# Clock2.net
KiCad netlist of a schematic drawn in EasyEDA Pro
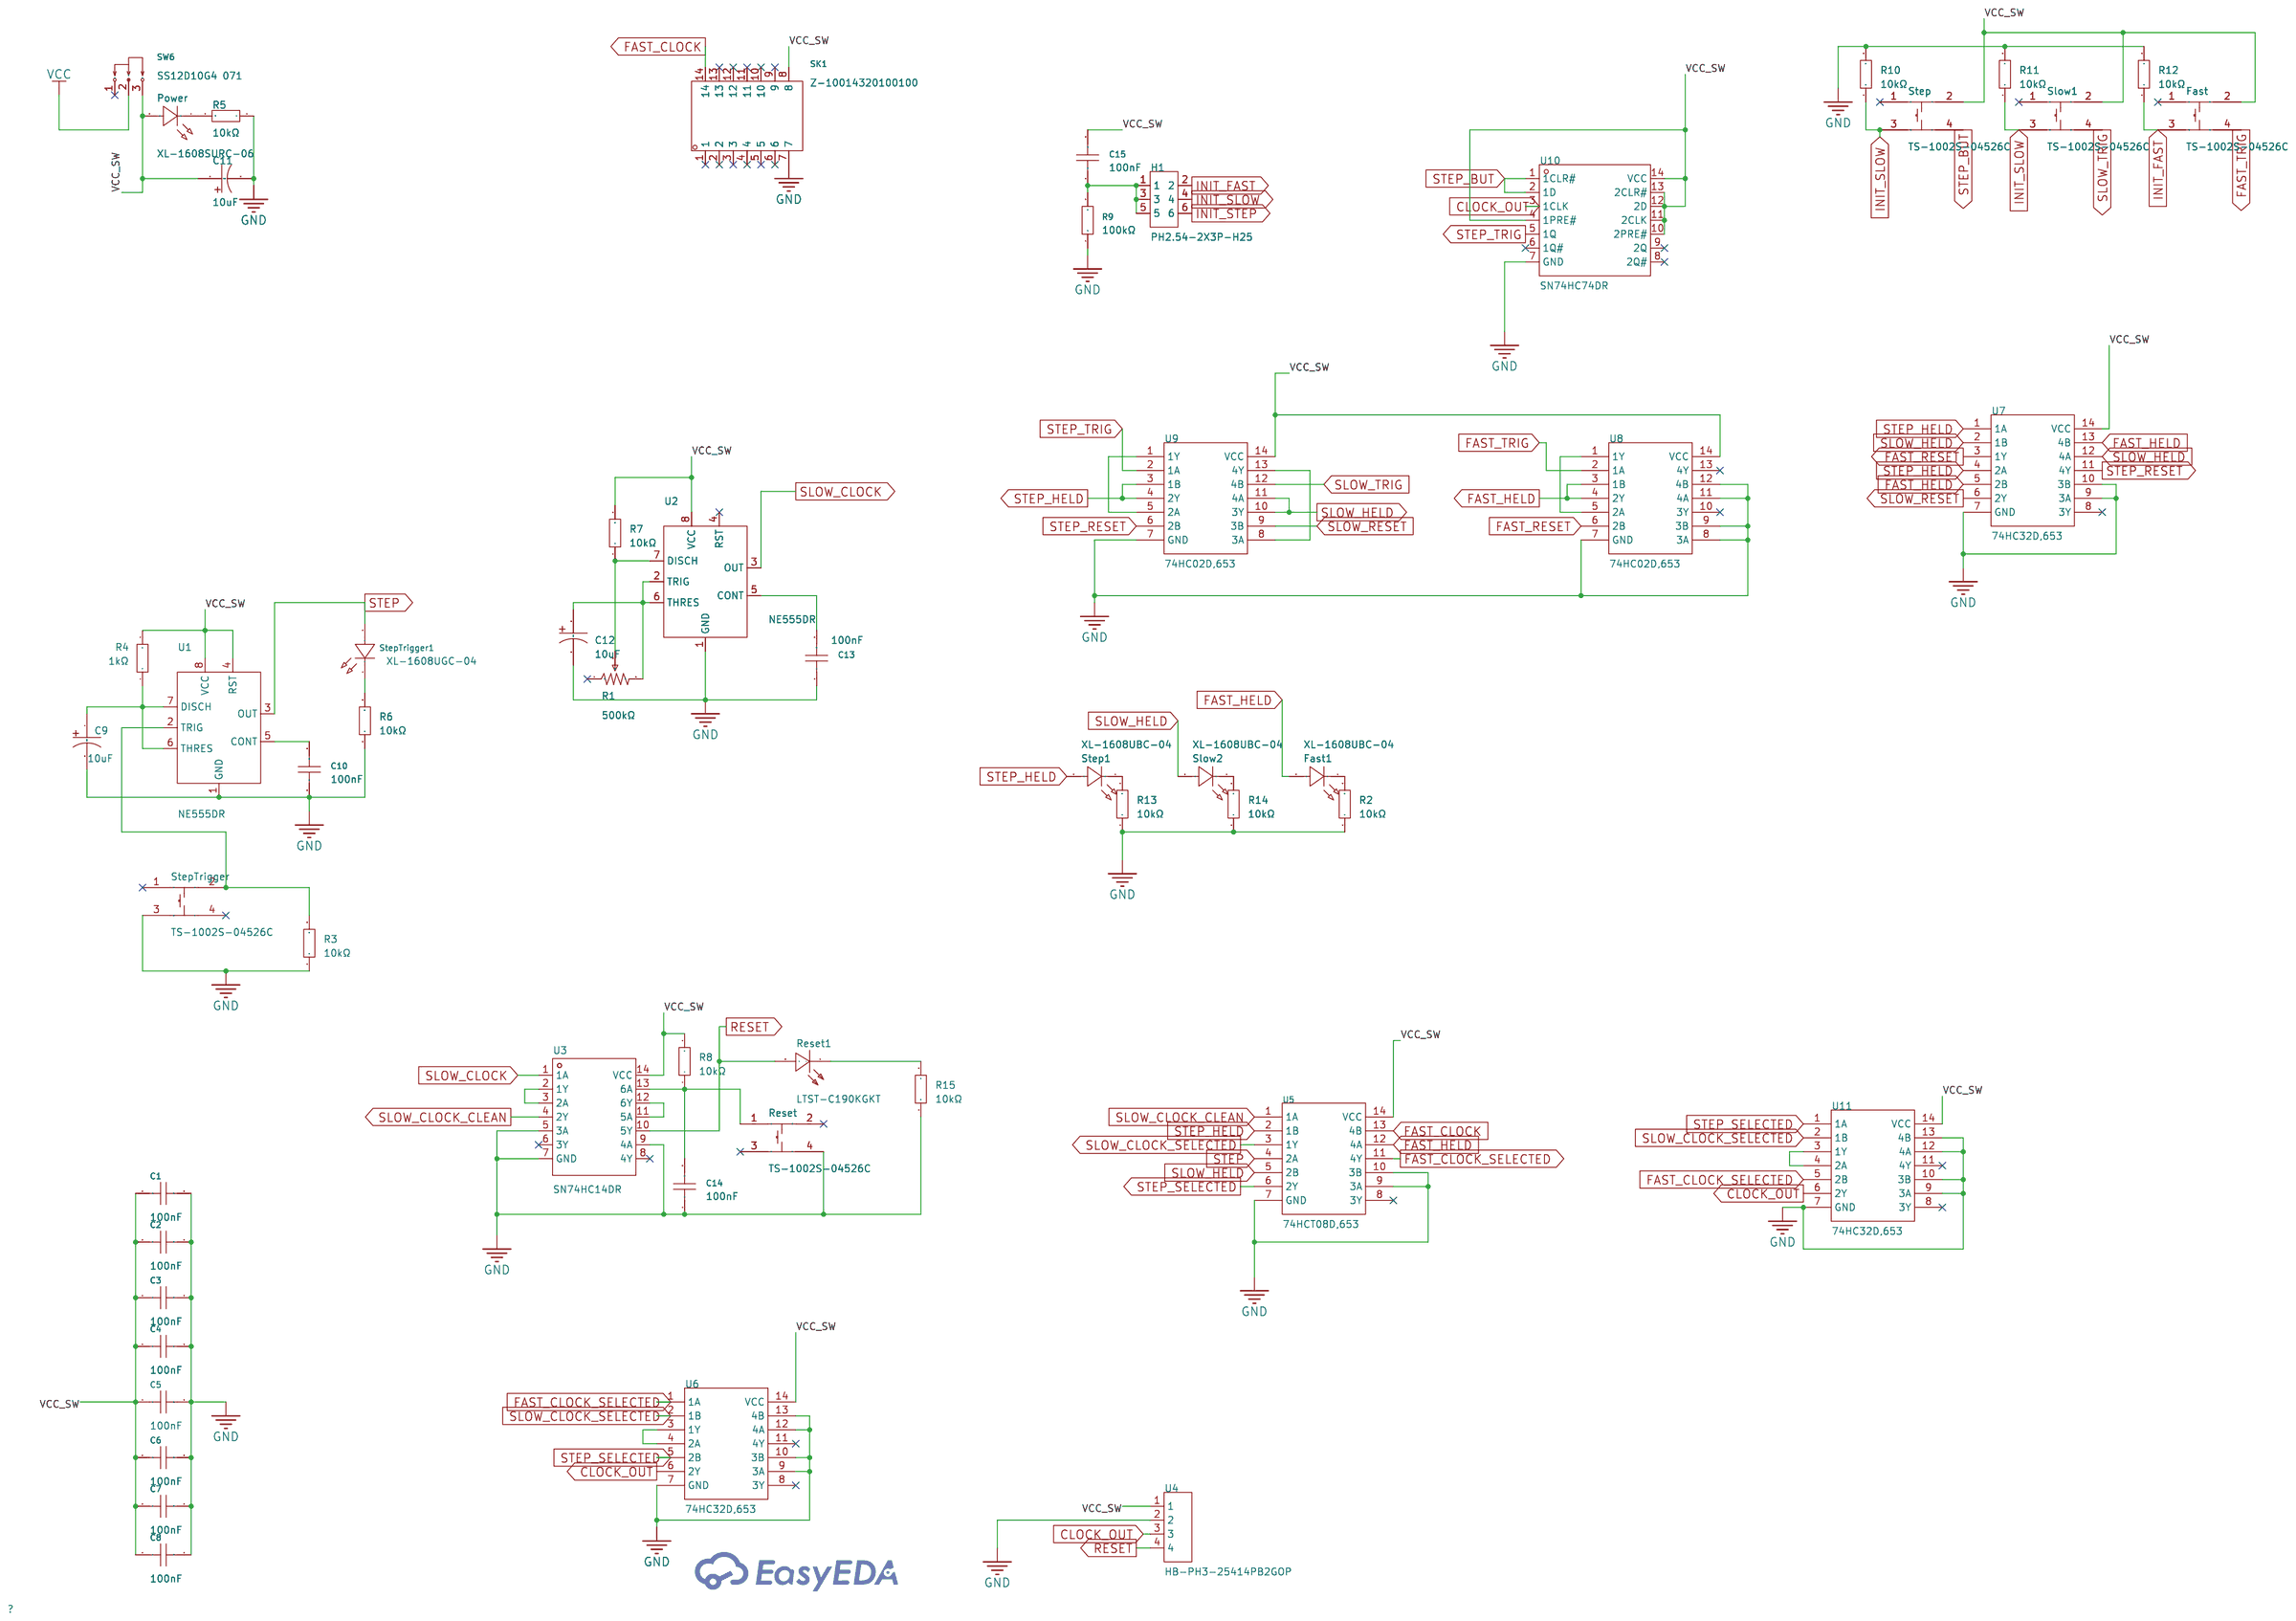
[diagram p0: schematic sheet]

(export (version "E")
  (design (tool "Eeschema 10.0.6"))
  (components
    (comp (ref "C1")
      (value "100nF")
      (footprint "easyedapro:C0603")
      (description "Capacitance:100nF Tolerance:±10% Tolerance:±10% Voltage Rating:50V Temperature Coefficient:X7R")
      (fields
        (field (name "Manufacturer Part") "CL10B104KB8NNNC")
        (field (name "Manufacturer") "SAMSUNG(三星)")
      )
      (libsource (lib "easyedapro") (part "CL10B104KB8NNNC"))
    )
    (comp (ref "C2")
      (value "100nF")
      (footprint "easyedapro:C0603")
      (description "Capacitance:100nF Tolerance:±10% Tolerance:±10% Voltage Rating:50V Temperature Coefficient:X7R")
      (fields
        (field (name "Manufacturer Part") "CL10B104KB8NNNC")
        (field (name "Manufacturer") "SAMSUNG(三星)")
      )
      (libsource (lib "easyedapro") (part "CL10B104KB8NNNC"))
    )
    (comp (ref "C3")
      (value "100nF")
      (footprint "easyedapro:C0603")
      (description "Capacitance:100nF Tolerance:±10% Tolerance:±10% Voltage Rating:50V Temperature Coefficient:X7R")
      (fields
        (field (name "Manufacturer Part") "CL10B104KB8NNNC")
        (field (name "Manufacturer") "SAMSUNG(三星)")
      )
      (libsource (lib "easyedapro") (part "CL10B104KB8NNNC"))
    )
    (comp (ref "C4")
      (value "100nF")
      (footprint "easyedapro:C0603")
      (description "Capacitance:100nF Tolerance:±10% Tolerance:±10% Voltage Rating:50V Temperature Coefficient:X7R")
      (fields
        (field (name "Manufacturer Part") "CL10B104KB8NNNC")
        (field (name "Manufacturer") "SAMSUNG(三星)")
      )
      (libsource (lib "easyedapro") (part "CL10B104KB8NNNC"))
    )
    (comp (ref "C5")
      (value "100nF")
      (footprint "easyedapro:C0603")
      (description "Capacitance:100nF Tolerance:±10% Tolerance:±10% Voltage Rating:50V Temperature Coefficient:X7R")
      (fields
        (field (name "Manufacturer Part") "CL10B104KB8NNNC")
        (field (name "Manufacturer") "SAMSUNG(三星)")
      )
      (libsource (lib "easyedapro") (part "CL10B104KB8NNNC"))
    )
    (comp (ref "C6")
      (value "100nF")
      (footprint "easyedapro:C0603")
      (description "Capacitance:100nF Tolerance:±10% Tolerance:±10% Voltage Rating:50V Temperature Coefficient:X7R")
      (fields
        (field (name "Manufacturer Part") "CL10B104KB8NNNC")
        (field (name "Manufacturer") "SAMSUNG(三星)")
      )
      (libsource (lib "easyedapro") (part "CL10B104KB8NNNC"))
    )
    (comp (ref "C7")
      (value "100nF")
      (footprint "easyedapro:C0603")
      (description "Capacitance:100nF Tolerance:±10% Tolerance:±10% Voltage Rating:50V Temperature Coefficient:X7R")
      (fields
        (field (name "Manufacturer Part") "CL10B104KB8NNNC")
        (field (name "Manufacturer") "SAMSUNG(三星)")
      )
      (libsource (lib "easyedapro") (part "CL10B104KB8NNNC"))
    )
    (comp (ref "C8")
      (value "100nF")
      (footprint "easyedapro:C0603")
      (description "Capacitance:100nF Tolerance:±10% Tolerance:±10% Voltage Rating:50V Temperature Coefficient:X7R")
      (fields
        (field (name "Manufacturer Part") "CL10B104KB8NNNC")
        (field (name "Manufacturer") "SAMSUNG(三星)")
      )
      (libsource (lib "easyedapro") (part "CL10B104KB8NNNC"))
    )
    (comp (ref "C9")
      (value "10uF")
      (footprint "easyedapro:CAP-TH_BD4.0-P1.50-D0.8-FD")
      (fields
        (field (name "Manufacturer Part") "KS1C100MB070A00CV0")
        (field (name "Manufacturer") "HUAWEI(华威集团)")
      )
      (libsource (lib "easyedapro") (part "KS1C100MB070A00CV0"))
    )
    (comp (ref "C10")
      (value "100nF")
      (footprint "easyedapro:C0603")
      (description "Capacitance:100nF Tolerance:±10% Tolerance:±10% Voltage Rating:50V Temperature Coefficient:X7R")
      (fields
        (field (name "Manufacturer Part") "CL10B104KB8NNNC")
        (field (name "Manufacturer") "SAMSUNG(三星)")
      )
      (libsource (lib "easyedapro") (part "CL10B104KB8NNNC"))
    )
    (comp (ref "C11")
      (value "10uF")
      (footprint "easyedapro:CAP-TH_BD4.0-P1.50-D0.8-FD")
      (fields
        (field (name "Manufacturer Part") "KS1C100MB070A00CV0")
        (field (name "Manufacturer") "HUAWEI(华威集团)")
      )
      (libsource (lib "easyedapro") (part "KS1C100MB070A00CV0"))
    )
    (comp (ref "C12")
      (value "10uF")
      (footprint "easyedapro:CAP-TH_BD4.0-P1.50-D0.8-FD")
      (fields
        (field (name "Manufacturer Part") "KS1C100MB070A00CV0")
        (field (name "Manufacturer") "HUAWEI(华威集团)")
      )
      (libsource (lib "easyedapro") (part "KS1C100MB070A00CV0"))
    )
    (comp (ref "C13")
      (value "100nF")
      (footprint "easyedapro:C0603")
      (description "Capacitance:100nF Tolerance:±10% Tolerance:±10% Voltage Rating:50V Temperature Coefficient:X7R")
      (fields
        (field (name "Manufacturer Part") "CL10B104KB8NNNC")
        (field (name "Manufacturer") "SAMSUNG(三星)")
      )
      (libsource (lib "easyedapro") (part "CL10B104KB8NNNC"))
    )
    (comp (ref "C14")
      (value "100nF")
      (footprint "easyedapro:C0603")
      (description "Capacitance:100nF Tolerance:±10% Tolerance:±10% Voltage Rating:50V Temperature Coefficient:X7R")
      (fields
        (field (name "Manufacturer Part") "CL10B104KB8NNNC")
        (field (name "Manufacturer") "SAMSUNG(三星)")
      )
      (libsource (lib "easyedapro") (part "CL10B104KB8NNNC"))
    )
    (comp (ref "C15")
      (value "100nF")
      (footprint "easyedapro:C0603")
      (description "Capacitance:100nF Tolerance:±10% Tolerance:±10% Voltage Rating:50V Temperature Coefficient:X7R")
      (fields
        (field (name "Manufacturer Part") "CL10B104KB8NNNC")
        (field (name "Manufacturer") "SAMSUNG(三星)")
      )
      (libsource (lib "easyedapro") (part "CL10B104KB8NNNC"))
    )
    (comp (ref "Fast")
      (value "TS-1002S-04526C")
      (footprint "easyedapro:SW-SMD_4P-L6.0-W6.0-P4.50-LS9.0-2")
      (fields (field (name "Manufacturer") "XUNPU(讯普)"))
      (libsource (lib "easyedapro") (part "TS-1002S-04526C"))
    )
    (comp (ref "Fast1")
      (value "XL-1608UBC-04")
      (footprint "easyedapro:LED0603-RD_BLUE")
      (fields (field (name "Manufacturer") "XINGLIGHT(成兴光)"))
      (libsource (lib "easyedapro") (part "XL-1608UBC-04"))
    )
    (comp (ref "H1")
      (value "PH2.54-2X3P-H25")
      (footprint "easyedapro:HDR-TH_6P-P2.54-V-M-R2-C3-S2.54-1")
      (fields (field (name "Manufacturer") "JXTCONN(聚兴泰)"))
      (libsource (lib "easyedapro") (part "PH2.54-2X3P-H25"))
    )
    (comp (ref "Power")
      (value "XL-1608SURC-06")
      (footprint "easyedapro:LED0603-RD_RED")
      (fields (field (name "Manufacturer") "XINGLIGHT(成兴光)"))
      (libsource (lib "easyedapro") (part "XL-1608SURC-06"))
    )
    (comp (ref "R1")
      (value "500kΩ")
      (footprint "easyedapro:RES-ADJ-TH_3P-L9.5-W9.5-P2.54-BL_3386P-EY5-504LF")
      (description "Resistance:500kΩ Voltage Rating:- Power(Watts):500mW Number of Turns:-")
      (fields (field (name "Manufacturer Part") "3386P-EY5-504LF") (field (name "Manufacturer") "BOURNS"))
      (libsource (lib "easyedapro") (part "3386P-EY5-504LF"))
    )
    (comp (ref "R2")
      (value "10kΩ")
      (footprint "easyedapro:R0603")
      (fields (field (name "Manufacturer Part") "RC0603FR-0710KL") (field (name "Manufacturer") "YAGEO(国巨)"))
      (libsource (lib "easyedapro") (part "RC0603FR-0710KL"))
    )
    (comp (ref "R3")
      (value "10kΩ")
      (footprint "easyedapro:R0603")
      (fields (field (name "Manufacturer Part") "RC0603FR-0710KL") (field (name "Manufacturer") "YAGEO(国巨)"))
      (libsource (lib "easyedapro") (part "RC0603FR-0710KL"))
    )
    (comp (ref "R4")
      (value "1kΩ")
      (footprint "easyedapro:R0603")
      (fields (field (name "Manufacturer Part") "RC0603FR-071KL") (field (name "Manufacturer") "YAGEO(国巨)"))
      (libsource (lib "easyedapro") (part "RC0603FR-071KL"))
    )
    (comp (ref "R5")
      (value "10kΩ")
      (footprint "easyedapro:R0603")
      (fields (field (name "Manufacturer Part") "RC0603FR-0710KL") (field (name "Manufacturer") "YAGEO(国巨)"))
      (libsource (lib "easyedapro") (part "RC0603FR-0710KL"))
    )
    (comp (ref "R6")
      (value "10kΩ")
      (footprint "easyedapro:R0603")
      (fields (field (name "Manufacturer Part") "RC0603FR-0710KL") (field (name "Manufacturer") "YAGEO(国巨)"))
      (libsource (lib "easyedapro") (part "RC0603FR-0710KL"))
    )
    (comp (ref "R7")
      (value "10kΩ")
      (footprint "easyedapro:R0603")
      (fields (field (name "Manufacturer Part") "RC0603FR-0710KL") (field (name "Manufacturer") "YAGEO(国巨)"))
      (libsource (lib "easyedapro") (part "RC0603FR-0710KL"))
    )
    (comp (ref "R8")
      (value "10kΩ")
      (footprint "easyedapro:R0603")
      (fields (field (name "Manufacturer Part") "RC0603FR-0710KL") (field (name "Manufacturer") "YAGEO(国巨)"))
      (libsource (lib "easyedapro") (part "RC0603FR-0710KL"))
    )
    (comp (ref "R9")
      (value "100kΩ")
      (footprint "easyedapro:R0603")
      (fields (field (name "Manufacturer Part") "RC0603FR-07100KL") (field (name "Manufacturer") "YAGEO(国巨)"))
      (libsource (lib "easyedapro") (part "RC0603FR-07100KL"))
    )
    (comp (ref "R10")
      (value "10kΩ")
      (footprint "easyedapro:R0603")
      (fields (field (name "Manufacturer Part") "RC0603FR-0710KL") (field (name "Manufacturer") "YAGEO(国巨)"))
      (libsource (lib "easyedapro") (part "RC0603FR-0710KL"))
    )
    (comp (ref "R11")
      (value "10kΩ")
      (footprint "easyedapro:R0603")
      (fields (field (name "Manufacturer Part") "RC0603FR-0710KL") (field (name "Manufacturer") "YAGEO(国巨)"))
      (libsource (lib "easyedapro") (part "RC0603FR-0710KL"))
    )
    (comp (ref "R12")
      (value "10kΩ")
      (footprint "easyedapro:R0603")
      (fields (field (name "Manufacturer Part") "RC0603FR-0710KL") (field (name "Manufacturer") "YAGEO(国巨)"))
      (libsource (lib "easyedapro") (part "RC0603FR-0710KL"))
    )
    (comp (ref "R13")
      (value "10kΩ")
      (footprint "easyedapro:R0603")
      (fields (field (name "Manufacturer Part") "RC0603FR-0710KL") (field (name "Manufacturer") "YAGEO(国巨)"))
      (libsource (lib "easyedapro") (part "RC0603FR-0710KL"))
    )
    (comp (ref "R14")
      (value "10kΩ")
      (footprint "easyedapro:R0603")
      (fields (field (name "Manufacturer Part") "RC0603FR-0710KL") (field (name "Manufacturer") "YAGEO(国巨)"))
      (libsource (lib "easyedapro") (part "RC0603FR-0710KL"))
    )
    (comp (ref "R15")
      (value "10kΩ")
      (footprint "easyedapro:R0603")
      (fields (field (name "Manufacturer Part") "RC0603FR-0710KL") (field (name "Manufacturer") "YAGEO(国巨)"))
      (libsource (lib "easyedapro") (part "RC0603FR-0710KL"))
    )
    (comp (ref "Reset")
      (value "TS-1002S-04526C")
      (footprint "easyedapro:SW-SMD_4P-L6.0-W6.0-P4.50-LS9.0-2")
      (fields (field (name "Manufacturer") "XUNPU(讯普)"))
      (libsource (lib "easyedapro") (part "TS-1002S-04526C"))
    )
    (comp (ref "Reset1")
      (value "LTST-C190KGKT")
      (footprint "easyedapro:LED0603-RD")
      (fields (field (name "Manufacturer") "LITEON(光宝)"))
      (libsource (lib "easyedapro") (part "LTST-C190KGKT"))
    )
    (comp (ref "SK1")
      (value "Z-10014320100100")
      (footprint "easyedapro:DIP-14_L17.8-W10.2-P2.54-BL")
      (fields (field (name "Manufacturer") "Nextron(正凌)"))
      (libsource (lib "easyedapro") (part "Z-10014320100100"))
    )
    (comp (ref "Slow1")
      (value "TS-1002S-04526C")
      (footprint "easyedapro:SW-SMD_4P-L6.0-W6.0-P4.50-LS9.0-2")
      (fields (field (name "Manufacturer") "XUNPU(讯普)"))
      (libsource (lib "easyedapro") (part "TS-1002S-04526C"))
    )
    (comp (ref "Slow2")
      (value "XL-1608UBC-04")
      (footprint "easyedapro:LED0603-RD_BLUE")
      (fields (field (name "Manufacturer") "XINGLIGHT(成兴光)"))
      (libsource (lib "easyedapro") (part "XL-1608UBC-04"))
    )
    (comp (ref "Step")
      (value "TS-1002S-04526C")
      (footprint "easyedapro:SW-SMD_4P-L6.0-W6.0-P4.50-LS9.0-2")
      (fields (field (name "Manufacturer") "XUNPU(讯普)"))
      (libsource (lib "easyedapro") (part "TS-1002S-04526C"))
    )
    (comp (ref "Step1")
      (value "XL-1608UBC-04")
      (footprint "easyedapro:LED0603-RD_BLUE")
      (fields (field (name "Manufacturer") "XINGLIGHT(成兴光)"))
      (libsource (lib "easyedapro") (part "XL-1608UBC-04"))
    )
    (comp (ref "StepTrigger")
      (value "TS-1002S-04526C")
      (footprint "easyedapro:SW-SMD_4P-L6.0-W6.0-P4.50-LS9.0-2")
      (fields (field (name "Manufacturer") "XUNPU(讯普)"))
      (libsource (lib "easyedapro") (part "TS-1002S-04526C"))
    )
    (comp (ref "StepTrigger1")
      (value "XL-1608UGC-04")
      (footprint "easyedapro:LED0603-RD_GREEN")
      (fields (field (name "Manufacturer") "XINGLIGHT(成兴光)"))
      (libsource (lib "easyedapro") (part "XL-1608UGC-04"))
    )
    (comp (ref "SW6")
      (value "SS12D10G4 071")
      (footprint "easyedapro:SW-TH_SHOU-HAN_SS12D10G4")
      (fields (field (name "Manufacturer") "SHOU HAN(首韩)"))
      (libsource (lib "easyedapro") (part "SS12D10G4 071"))
    )
    (comp (ref "U1")
      (value "NE555DR")
      (footprint "easyedapro:SOIC-8_L4.9-W3.9-P1.27-LS6.0-BL")
      (fields (field (name "Manufacturer") "TI(德州仪器)"))
      (libsource (lib "easyedapro") (part "NE555DR"))
    )
    (comp (ref "U2")
      (value "NE555DR")
      (footprint "easyedapro:SOIC-8_L4.9-W3.9-P1.27-LS6.0-BL")
      (fields (field (name "Manufacturer") "TI(德州仪器)"))
      (libsource (lib "easyedapro") (part "NE555DR"))
    )
    (comp (ref "U3")
      (value "SN74HC14DR")
      (footprint "easyedapro:SOIC-14_L8.7-W3.9-P1.27-LS6.0-BL")
      (fields (field (name "Manufacturer") "TI(德州仪器)"))
      (libsource (lib "easyedapro") (part "SN74HC14DR"))
    )
    (comp (ref "U4")
      (value "HB-PH3-25414PB2GOP")
      (footprint "easyedapro:HDR-TH_4P-P2.54-V-M")
      (fields (field (name "Manufacturer") "HANBO(汉博)"))
      (libsource (lib "easyedapro") (part "HB-PH3-25414PB2GOP"))
    )
    (comp (ref "U5")
      (value "74HCT08D,653")
      (footprint "easyedapro:SOIC-14_L8.7-W3.9-P1.27-LS6.0-BL")
      (fields (field (name "Manufacturer") "Nexperia(安世)"))
      (libsource (lib "easyedapro") (part "74HCT08D,653"))
    )
    (comp (ref "U6")
      (value "74HC32D,653")
      (footprint "easyedapro:SOIC-14_L8.7-W3.9-P1.27-LS6.0-BL")
      (fields (field (name "Manufacturer") "Nexperia(安世)"))
      (libsource (lib "easyedapro") (part "74HC32D,653"))
    )
    (comp (ref "U7")
      (value "74HC32D,653")
      (footprint "easyedapro:SOIC-14_L8.7-W3.9-P1.27-LS6.0-BL")
      (fields (field (name "Manufacturer") "Nexperia(安世)"))
      (libsource (lib "easyedapro") (part "74HC32D,653"))
    )
    (comp (ref "U8")
      (value "74HC02D,653")
      (footprint "easyedapro:SOIC-14_L8.7-W3.9-P1.27-LS6.0-BL")
      (fields (field (name "Manufacturer") "Nexperia(安世)"))
      (libsource (lib "easyedapro") (part "74HC02D,653"))
    )
    (comp (ref "U9")
      (value "74HC02D,653")
      (footprint "easyedapro:SOIC-14_L8.7-W3.9-P1.27-LS6.0-BL")
      (fields (field (name "Manufacturer") "Nexperia(安世)"))
      (libsource (lib "easyedapro") (part "74HC02D,653"))
    )
    (comp (ref "U10")
      (value "SN74HC74DR")
      (footprint "easyedapro:SOIC-14_L8.7-W3.9-P1.27-LS6.0-BL")
      (fields (field (name "Manufacturer") "TI(德州仪器)"))
      (libsource (lib "easyedapro") (part "SN74HC74DR"))
    )
    (comp (ref "U11")
      (value "74HC32D,653")
      (footprint "easyedapro:SOIC-14_L8.7-W3.9-P1.27-LS6.0-BL")
      (fields (field (name "Manufacturer") "Nexperia(安世)"))
      (libsource (lib "easyedapro") (part "74HC32D,653"))
    )
  )
  (nets
    (net (code "1") (name "/VCC_SW") (class "Default")
      (node (ref "C1") (pin "1") (pinfunction "1_1") (pintype "input"))
      (node (ref "C11") (pin "1") (pinfunction "1_1") (pintype "unspecified"))
      (node (ref "C15") (pin "2") (pinfunction "2_2") (pintype "input"))
      (node (ref "C2") (pin "1") (pinfunction "1_1") (pintype "input"))
      (node (ref "C3") (pin "1") (pinfunction "1_1") (pintype "input"))
      (node (ref "C4") (pin "1") (pinfunction "1_1") (pintype "input"))
      (node (ref "C5") (pin "1") (pinfunction "1_1") (pintype "input"))
      (node (ref "C6") (pin "1") (pinfunction "1_1") (pintype "input"))
      (node (ref "C7") (pin "1") (pinfunction "1_1") (pintype "input"))
      (node (ref "C8") (pin "1") (pinfunction "1_1") (pintype "input"))
      (node (ref "Fast") (pin "2") (pinfunction "2_2") (pintype "unspecified"))
      (node (ref "Power") (pin "2") (pinfunction "A_2") (pintype "unspecified"))
      (node (ref "R4") (pin "2") (pinfunction "2_2") (pintype "input"))
      (node (ref "R7") (pin "2") (pinfunction "2_2") (pintype "input"))
      (node (ref "R8") (pin "2") (pinfunction "2_2") (pintype "input"))
      (node (ref "SK1") (pin "8") (pinfunction "8_8") (pintype "input"))
      (node (ref "SW6") (pin "3") (pinfunction "3_3") (pintype "input"))
      (node (ref "Slow1") (pin "2") (pinfunction "2_2") (pintype "unspecified"))
      (node (ref "Step") (pin "2") (pinfunction "2_2") (pintype "unspecified"))
      (node (ref "U1") (pin "4") (pinfunction "RST_4") (pintype "unspecified"))
      (node (ref "U1") (pin "8") (pinfunction "VCC_8") (pintype "unspecified"))
      (node (ref "U10") (pin "10") (pinfunction "2PRE#_10") (pintype "unspecified"))
      (node (ref "U10") (pin "11") (pinfunction "2CLK_11") (pintype "unspecified"))
      (node (ref "U10") (pin "12") (pinfunction "2D_12") (pintype "unspecified"))
      (node (ref "U10") (pin "13") (pinfunction "2CLR#_13") (pintype "unspecified"))
      (node (ref "U10") (pin "14") (pinfunction "VCC_14") (pintype "unspecified"))
      (node (ref "U10") (pin "4") (pinfunction "1PRE#_4") (pintype "unspecified"))
      (node (ref "U11") (pin "14") (pinfunction "VCC_14") (pintype "input"))
      (node (ref "U2") (pin "8") (pinfunction "VCC_8") (pintype "unspecified"))
      (node (ref "U3") (pin "14") (pinfunction "VCC_14") (pintype "unspecified"))
      (node (ref "U4") (pin "1") (pinfunction "1_1") (pintype "unspecified"))
      (node (ref "U5") (pin "14") (pinfunction "VCC_14") (pintype "input"))
      (node (ref "U6") (pin "14") (pinfunction "VCC_14") (pintype "input"))
      (node (ref "U7") (pin "14") (pinfunction "VCC_14") (pintype "input"))
      (node (ref "U8") (pin "14") (pinfunction "VCC_14") (pintype "input"))
      (node (ref "U9") (pin "14") (pinfunction "VCC_14") (pintype "input"))
    )
    (net (code "2") (name "CLOCK_OUT") (class "Default")
      (node (ref "U10") (pin "3") (pinfunction "1CLK_3") (pintype "unspecified"))
      (node (ref "U11") (pin "6") (pinfunction "2Y_6") (pintype "input"))
      (node (ref "U4") (pin "3") (pinfunction "3_3") (pintype "unspecified"))
      (node (ref "U6") (pin "6") (pinfunction "2Y_6") (pintype "input"))
    )
    (net (code "3") (name "FAST_CLOCK") (class "Default")
      (node (ref "SK1") (pin "14") (pinfunction "14_14") (pintype "input"))
      (node (ref "U5") (pin "13") (pinfunction "4B_13") (pintype "input"))
    )
    (net (code "4") (name "FAST_CLOCK_SELECTED") (class "Default")
      (node (ref "U11") (pin "5") (pinfunction "2B_5") (pintype "input"))
      (node (ref "U5") (pin "11") (pinfunction "4Y_11") (pintype "input"))
      (node (ref "U6") (pin "1") (pinfunction "1A_1") (pintype "input"))
    )
    (net (code "5") (name "FAST_HELD") (class "Default")
      (node (ref "Fast1") (pin "2") (pinfunction "A_2") (pintype "unspecified"))
      (node (ref "U5") (pin "12") (pinfunction "4A_12") (pintype "input"))
      (node (ref "U7") (pin "13") (pinfunction "4B_13") (pintype "input"))
      (node (ref "U7") (pin "5") (pinfunction "2B_5") (pintype "input"))
      (node (ref "U8") (pin "3") (pinfunction "1B_3") (pintype "input"))
      (node (ref "U8") (pin "4") (pinfunction "2Y_4") (pintype "input"))
    )
    (net (code "6") (name "FAST_RESET") (class "Default")
      (node (ref "U7") (pin "3") (pinfunction "1Y_3") (pintype "input"))
      (node (ref "U8") (pin "6") (pinfunction "2B_6") (pintype "input"))
    )
    (net (code "7") (name "FAST_TRIG") (class "Default")
      (node (ref "Fast") (pin "4") (pinfunction "4_4") (pintype "unspecified"))
      (node (ref "U8") (pin "2") (pinfunction "1A_2") (pintype "input"))
    )
    (net (code "8") (name "GND") (class "Default")
      (node (ref "C1") (pin "2") (pinfunction "2_2") (pintype "input"))
      (node (ref "C10") (pin "1") (pinfunction "1_1") (pintype "input"))
      (node (ref "C11") (pin "2") (pinfunction "2_2") (pintype "unspecified"))
      (node (ref "C12") (pin "2") (pinfunction "2_2") (pintype "unspecified"))
      (node (ref "C13") (pin "1") (pinfunction "1_1") (pintype "input"))
      (node (ref "C14") (pin "1") (pinfunction "1_1") (pintype "input"))
      (node (ref "C2") (pin "2") (pinfunction "2_2") (pintype "input"))
      (node (ref "C3") (pin "2") (pinfunction "2_2") (pintype "input"))
      (node (ref "C4") (pin "2") (pinfunction "2_2") (pintype "input"))
      (node (ref "C5") (pin "2") (pinfunction "2_2") (pintype "input"))
      (node (ref "C6") (pin "2") (pinfunction "2_2") (pintype "input"))
      (node (ref "C7") (pin "2") (pinfunction "2_2") (pintype "input"))
      (node (ref "C8") (pin "2") (pinfunction "2_2") (pintype "input"))
      (node (ref "C9") (pin "2") (pinfunction "2_2") (pintype "unspecified"))
      (node (ref "R10") (pin "2") (pinfunction "2_2") (pintype "input"))
      (node (ref "R11") (pin "2") (pinfunction "2_2") (pintype "input"))
      (node (ref "R12") (pin "2") (pinfunction "2_2") (pintype "input"))
      (node (ref "R13") (pin "1") (pinfunction "1_1") (pintype "input"))
      (node (ref "R14") (pin "1") (pinfunction "1_1") (pintype "input"))
      (node (ref "R15") (pin "1") (pinfunction "1_1") (pintype "input"))
      (node (ref "R2") (pin "1") (pinfunction "1_1") (pintype "input"))
      (node (ref "R3") (pin "1") (pinfunction "1_1") (pintype "input"))
      (node (ref "R5") (pin "1") (pinfunction "1_1") (pintype "input"))
      (node (ref "R6") (pin "1") (pinfunction "1_1") (pintype "input"))
      (node (ref "R9") (pin "1") (pinfunction "1_1") (pintype "input"))
      (node (ref "Reset") (pin "4") (pinfunction "4_4") (pintype "unspecified"))
      (node (ref "SK1") (pin "7") (pinfunction "7_7") (pintype "input"))
      (node (ref "StepTrigger") (pin "3") (pinfunction "3_3") (pintype "unspecified"))
      (node (ref "U1") (pin "1") (pinfunction "GND_1") (pintype "unspecified"))
      (node (ref "U10") (pin "7") (pinfunction "GND_7") (pintype "unspecified"))
      (node (ref "U11") (pin "10") (pinfunction "3B_10") (pintype "input"))
      (node (ref "U11") (pin "12") (pinfunction "4A_12") (pintype "input"))
      (node (ref "U11") (pin "13") (pinfunction "4B_13") (pintype "input"))
      (node (ref "U11") (pin "7") (pinfunction "GND_7") (pintype "input"))
      (node (ref "U11") (pin "9") (pinfunction "3A_9") (pintype "input"))
      (node (ref "U2") (pin "1") (pinfunction "GND_1") (pintype "unspecified"))
      (node (ref "U3") (pin "5") (pinfunction "3A_5") (pintype "unspecified"))
      (node (ref "U3") (pin "7") (pinfunction "GND_7") (pintype "unspecified"))
      (node (ref "U3") (pin "9") (pinfunction "4A_9") (pintype "unspecified"))
      (node (ref "U4") (pin "2") (pinfunction "2_2") (pintype "unspecified"))
      (node (ref "U5") (pin "10") (pinfunction "3B_10") (pintype "input"))
      (node (ref "U5") (pin "7") (pinfunction "GND_7") (pintype "input"))
      (node (ref "U5") (pin "9") (pinfunction "3A_9") (pintype "input"))
      (node (ref "U6") (pin "10") (pinfunction "3B_10") (pintype "input"))
      (node (ref "U6") (pin "12") (pinfunction "4A_12") (pintype "input"))
      (node (ref "U6") (pin "13") (pinfunction "4B_13") (pintype "input"))
      (node (ref "U6") (pin "7") (pinfunction "GND_7") (pintype "input"))
      (node (ref "U6") (pin "9") (pinfunction "3A_9") (pintype "input"))
      (node (ref "U7") (pin "10") (pinfunction "3B_10") (pintype "input"))
      (node (ref "U7") (pin "7") (pinfunction "GND_7") (pintype "input"))
      (node (ref "U7") (pin "9") (pinfunction "3A_9") (pintype "input"))
      (node (ref "U8") (pin "11") (pinfunction "4A_11") (pintype "input"))
      (node (ref "U8") (pin "12") (pinfunction "4B_12") (pintype "input"))
      (node (ref "U8") (pin "7") (pinfunction "GND_7") (pintype "input"))
      (node (ref "U8") (pin "8") (pinfunction "3A_8") (pintype "input"))
      (node (ref "U8") (pin "9") (pinfunction "3B_9") (pintype "input"))
      (node (ref "U9") (pin "7") (pinfunction "GND_7") (pintype "input"))
    )
    (net (code "9") (name "INIT_FAST") (class "Default")
      (node (ref "Fast") (pin "3") (pinfunction "3_3") (pintype "unspecified"))
      (node (ref "H1") (pin "2") (pinfunction "2_2") (pintype "unspecified"))
      (node (ref "R12") (pin "1") (pinfunction "1_1") (pintype "input"))
    )
    (net (code "10") (name "INIT_SLOW") (class "Default")
      (node (ref "H1") (pin "4") (pinfunction "4_4") (pintype "unspecified"))
      (node (ref "R10") (pin "1") (pinfunction "1_1") (pintype "input"))
      (node (ref "R11") (pin "1") (pinfunction "1_1") (pintype "input"))
      (node (ref "Slow1") (pin "3") (pinfunction "3_3") (pintype "unspecified"))
      (node (ref "Step") (pin "3") (pinfunction "3_3") (pintype "unspecified"))
    )
    (net (code "11") (name "INIT_STEP") (class "Default")
      (node (ref "H1") (pin "6") (pinfunction "6_6") (pintype "unspecified"))
    )
    (net (code "12") (name "Net-(C15-Pad1)") (class "Default")
      (node (ref "C15") (pin "1") (pinfunction "1_1") (pintype "input"))
      (node (ref "H1") (pin "1") (pinfunction "1_1") (pintype "unspecified"))
      (node (ref "H1") (pin "3") (pinfunction "3_3") (pintype "unspecified"))
      (node (ref "H1") (pin "5") (pinfunction "5_5") (pintype "unspecified"))
      (node (ref "R9") (pin "2") (pinfunction "2_2") (pintype "input"))
    )
    (net (code "13") (name "Net-(Fast1-K)") (class "Default")
      (node (ref "Fast1") (pin "1") (pinfunction "K_1") (pintype "unspecified"))
      (node (ref "R2") (pin "2") (pinfunction "2_2") (pintype "input"))
    )
    (net (code "14") (name "Net-(Power-K)") (class "Default")
      (node (ref "Power") (pin "1") (pinfunction "K_1") (pintype "unspecified"))
      (node (ref "R5") (pin "2") (pinfunction "2_2") (pintype "input"))
    )
    (net (code "15") (name "Net-(R1-CW)") (class "Default")
      (node (ref "C12") (pin "1") (pinfunction "1_1") (pintype "unspecified"))
      (node (ref "R1") (pin "3") (pinfunction "CW_3") (pintype "unspecified"))
      (node (ref "U2") (pin "2") (pinfunction "TRIG_2") (pintype "unspecified"))
      (node (ref "U2") (pin "6") (pinfunction "THRES_6") (pintype "unspecified"))
    )
    (net (code "16") (name "Net-(R1-WIPER)") (class "Default")
      (node (ref "R1") (pin "2") (pinfunction "WIPER_2") (pintype "unspecified"))
      (node (ref "R7") (pin "1") (pinfunction "1_1") (pintype "input"))
      (node (ref "U2") (pin "7") (pinfunction "DISCH_7") (pintype "unspecified"))
    )
    (net (code "17") (name "Net-(Reset1--)") (class "Default")
      (node (ref "R15") (pin "2") (pinfunction "2_2") (pintype "input"))
      (node (ref "Reset1") (pin "1") (pinfunction "-_1") (pintype "unspecified"))
    )
    (net (code "18") (name "Net-(Slow2-K)") (class "Default")
      (node (ref "R14") (pin "2") (pinfunction "2_2") (pintype "input"))
      (node (ref "Slow2") (pin "1") (pinfunction "K_1") (pintype "unspecified"))
    )
    (net (code "19") (name "Net-(Step1-K)") (class "Default")
      (node (ref "R13") (pin "2") (pinfunction "2_2") (pintype "input"))
      (node (ref "Step1") (pin "1") (pinfunction "K_1") (pintype "unspecified"))
    )
    (net (code "20") (name "Net-(StepTrigger1-K)") (class "Default")
      (node (ref "R6") (pin "2") (pinfunction "2_2") (pintype "input"))
      (node (ref "StepTrigger1") (pin "1") (pinfunction "K_1") (pintype "input"))
    )
    (net (code "21") (name "Net-(U1-CONT)") (class "Default")
      (node (ref "C10") (pin "2") (pinfunction "2_2") (pintype "input"))
      (node (ref "U1") (pin "5") (pinfunction "CONT_5") (pintype "unspecified"))
    )
    (net (code "22") (name "Net-(U1-DISCH)") (class "Default")
      (node (ref "C9") (pin "1") (pinfunction "1_1") (pintype "unspecified"))
      (node (ref "R4") (pin "1") (pinfunction "1_1") (pintype "input"))
      (node (ref "U1") (pin "6") (pinfunction "THRES_6") (pintype "unspecified"))
      (node (ref "U1") (pin "7") (pinfunction "DISCH_7") (pintype "unspecified"))
    )
    (net (code "23") (name "Net-(U1-TRIG)") (class "Default")
      (node (ref "R3") (pin "2") (pinfunction "2_2") (pintype "input"))
      (node (ref "StepTrigger") (pin "2") (pinfunction "2_2") (pintype "unspecified"))
      (node (ref "U1") (pin "2") (pinfunction "TRIG_2") (pintype "unspecified"))
    )
    (net (code "24") (name "Net-(U2-CONT)") (class "Default")
      (node (ref "C13") (pin "2") (pinfunction "2_2") (pintype "input"))
      (node (ref "U2") (pin "5") (pinfunction "CONT_5") (pintype "unspecified"))
    )
    (net (code "25") (name "Net-(U3-1Y)") (class "Default")
      (node (ref "U3") (pin "2") (pinfunction "1Y_2") (pintype "unspecified"))
      (node (ref "U3") (pin "3") (pinfunction "2A_3") (pintype "unspecified"))
    )
    (net (code "26") (name "Net-(U3-5A)") (class "Default")
      (node (ref "U3") (pin "11") (pinfunction "5A_11") (pintype "unspecified"))
      (node (ref "U3") (pin "12") (pinfunction "6Y_12") (pintype "unspecified"))
    )
    (net (code "27") (name "Net-(U3-6A)") (class "Default")
      (node (ref "C14") (pin "2") (pinfunction "2_2") (pintype "input"))
      (node (ref "R8") (pin "1") (pinfunction "1_1") (pintype "input"))
      (node (ref "Reset") (pin "1") (pinfunction "1_1") (pintype "unspecified"))
      (node (ref "U3") (pin "13") (pinfunction "6A_13") (pintype "unspecified"))
    )
    (net (code "28") (name "Net-(U6-1Y)") (class "Default")
      (node (ref "U6") (pin "3") (pinfunction "1Y_3") (pintype "input"))
      (node (ref "U6") (pin "4") (pinfunction "2A_4") (pintype "input"))
    )
    (net (code "29") (name "Net-(U8-1Y)") (class "Default")
      (node (ref "U8") (pin "1") (pinfunction "1Y_1") (pintype "input"))
      (node (ref "U8") (pin "5") (pinfunction "2A_5") (pintype "input"))
    )
    (net (code "30") (name "Net-(U9-1Y)") (class "Default")
      (node (ref "U9") (pin "1") (pinfunction "1Y_1") (pintype "input"))
      (node (ref "U9") (pin "5") (pinfunction "2A_5") (pintype "input"))
    )
    (net (code "31") (name "Net-(U9-3A)") (class "Default")
      (node (ref "U9") (pin "13") (pinfunction "4Y_13") (pintype "input"))
      (node (ref "U9") (pin "8") (pinfunction "3A_8") (pintype "input"))
    )
    (net (code "32") (name "Net-(U11-1Y)") (class "Default")
      (node (ref "U11") (pin "3") (pinfunction "1Y_3") (pintype "input"))
      (node (ref "U11") (pin "4") (pinfunction "2A_4") (pintype "input"))
    )
    (net (code "33") (name "RESET") (class "Default")
      (node (ref "Reset1") (pin "2") (pinfunction "+_2") (pintype "unspecified"))
      (node (ref "U3") (pin "10") (pinfunction "5Y_10") (pintype "unspecified"))
      (node (ref "U4") (pin "4") (pinfunction "4_4") (pintype "unspecified"))
    )
    (net (code "34") (name "SLOW_CLOCK") (class "Default")
      (node (ref "U2") (pin "3") (pinfunction "OUT_3") (pintype "unspecified"))
      (node (ref "U3") (pin "1") (pinfunction "1A_1") (pintype "unspecified"))
    )
    (net (code "35") (name "SLOW_CLOCK_CLEAN") (class "Default")
      (node (ref "U3") (pin "4") (pinfunction "2Y_4") (pintype "unspecified"))
      (node (ref "U5") (pin "1") (pinfunction "1A_1") (pintype "input"))
    )
    (net (code "36") (name "SLOW_CLOCK_SELECTED") (class "Default")
      (node (ref "U11") (pin "2") (pinfunction "1B_2") (pintype "input"))
      (node (ref "U5") (pin "3") (pinfunction "1Y_3") (pintype "input"))
      (node (ref "U6") (pin "2") (pinfunction "1B_2") (pintype "input"))
    )
    (net (code "37") (name "SLOW_HELD") (class "Default")
      (node (ref "Slow2") (pin "2") (pinfunction "A_2") (pintype "unspecified"))
      (node (ref "U5") (pin "5") (pinfunction "2B_5") (pintype "input"))
      (node (ref "U7") (pin "12") (pinfunction "4A_12") (pintype "input"))
      (node (ref "U7") (pin "2") (pinfunction "1B_2") (pintype "input"))
      (node (ref "U9") (pin "10") (pinfunction "3Y_10") (pintype "input"))
      (node (ref "U9") (pin "11") (pinfunction "4A_11") (pintype "input"))
    )
    (net (code "38") (name "SLOW_RESET") (class "Default")
      (node (ref "U7") (pin "6") (pinfunction "2Y_6") (pintype "input"))
      (node (ref "U9") (pin "9") (pinfunction "3B_9") (pintype "input"))
    )
    (net (code "39") (name "SLOW_TRIG") (class "Default")
      (node (ref "Slow1") (pin "4") (pinfunction "4_4") (pintype "unspecified"))
      (node (ref "U9") (pin "12") (pinfunction "4B_12") (pintype "input"))
    )
    (net (code "40") (name "STEP") (class "Default")
      (node (ref "StepTrigger1") (pin "2") (pinfunction "A_2") (pintype "input"))
      (node (ref "U1") (pin "3") (pinfunction "OUT_3") (pintype "unspecified"))
      (node (ref "U5") (pin "4") (pinfunction "2A_4") (pintype "input"))
    )
    (net (code "41") (name "STEP_BUT") (class "Default")
      (node (ref "Step") (pin "4") (pinfunction "4_4") (pintype "unspecified"))
      (node (ref "U10") (pin "1") (pinfunction "1CLR#_1") (pintype "unspecified"))
      (node (ref "U10") (pin "2") (pinfunction "1D_2") (pintype "unspecified"))
    )
    (net (code "42") (name "STEP_HELD") (class "Default")
      (node (ref "Step1") (pin "2") (pinfunction "A_2") (pintype "unspecified"))
      (node (ref "U5") (pin "2") (pinfunction "1B_2") (pintype "input"))
      (node (ref "U7") (pin "1") (pinfunction "1A_1") (pintype "input"))
      (node (ref "U7") (pin "4") (pinfunction "2A_4") (pintype "input"))
      (node (ref "U9") (pin "3") (pinfunction "1B_3") (pintype "input"))
      (node (ref "U9") (pin "4") (pinfunction "2Y_4") (pintype "input"))
    )
    (net (code "43") (name "STEP_RESET") (class "Default")
      (node (ref "U7") (pin "11") (pinfunction "4Y_11") (pintype "input"))
      (node (ref "U9") (pin "6") (pinfunction "2B_6") (pintype "input"))
    )
    (net (code "44") (name "STEP_SELECTED") (class "Default")
      (node (ref "U11") (pin "1") (pinfunction "1A_1") (pintype "input"))
      (node (ref "U5") (pin "6") (pinfunction "2Y_6") (pintype "input"))
      (node (ref "U6") (pin "5") (pinfunction "2B_5") (pintype "input"))
    )
    (net (code "45") (name "STEP_TRIG") (class "Default")
      (node (ref "U10") (pin "5") (pinfunction "1Q_5") (pintype "unspecified"))
      (node (ref "U9") (pin "2") (pinfunction "1A_2") (pintype "input"))
    )
    (net (code "46") (name "VCC") (class "Default")
      (node (ref "SW6") (pin "2") (pinfunction "2_2") (pintype "input"))
    )
    (net (code "47") (name "unconnected-(Fast-Pad1)") (class "Default")
      (node (ref "Fast") (pin "1") (pinfunction "1_1") (pintype "unspecified+no_connect"))
    )
    (net (code "48") (name "unconnected-(R1-CCW-Pad1)") (class "Default")
      (node (ref "R1") (pin "1") (pinfunction "CCW_1") (pintype "unspecified+no_connect"))
    )
    (net (code "49") (name "unconnected-(Reset-Pad2)") (class "Default")
      (node (ref "Reset") (pin "2") (pinfunction "2_2") (pintype "unspecified+no_connect"))
    )
    (net (code "50") (name "unconnected-(Reset-Pad3)") (class "Default")
      (node (ref "Reset") (pin "3") (pinfunction "3_3") (pintype "unspecified+no_connect"))
    )
    (net (code "51") (name "unconnected-(SK1-Pad1)") (class "Default")
      (node (ref "SK1") (pin "1") (pinfunction "1_1") (pintype "input+no_connect"))
    )
    (net (code "52") (name "unconnected-(SK1-Pad2)") (class "Default")
      (node (ref "SK1") (pin "2") (pinfunction "2_2") (pintype "input+no_connect"))
    )
    (net (code "53") (name "unconnected-(SK1-Pad3)") (class "Default")
      (node (ref "SK1") (pin "3") (pinfunction "3_3") (pintype "input+no_connect"))
    )
    (net (code "54") (name "unconnected-(SK1-Pad4)") (class "Default")
      (node (ref "SK1") (pin "4") (pinfunction "4_4") (pintype "input+no_connect"))
    )
    (net (code "55") (name "unconnected-(SK1-Pad5)") (class "Default")
      (node (ref "SK1") (pin "5") (pinfunction "5_5") (pintype "input+no_connect"))
    )
    (net (code "56") (name "unconnected-(SK1-Pad6)") (class "Default")
      (node (ref "SK1") (pin "6") (pinfunction "6_6") (pintype "input+no_connect"))
    )
    (net (code "57") (name "unconnected-(SK1-Pad9)") (class "Default")
      (node (ref "SK1") (pin "9") (pinfunction "9_9") (pintype "input+no_connect"))
    )
    (net (code "58") (name "unconnected-(SK1-Pad10)") (class "Default")
      (node (ref "SK1") (pin "10") (pinfunction "10_10") (pintype "input+no_connect"))
    )
    (net (code "59") (name "unconnected-(SK1-Pad11)") (class "Default")
      (node (ref "SK1") (pin "11") (pinfunction "11_11") (pintype "input+no_connect"))
    )
    (net (code "60") (name "unconnected-(SK1-Pad12)") (class "Default")
      (node (ref "SK1") (pin "12") (pinfunction "12_12") (pintype "input+no_connect"))
    )
    (net (code "61") (name "unconnected-(SK1-Pad13)") (class "Default")
      (node (ref "SK1") (pin "13") (pinfunction "13_13") (pintype "input+no_connect"))
    )
    (net (code "62") (name "unconnected-(SW6-Pad1)") (class "Default")
      (node (ref "SW6") (pin "1") (pinfunction "1_1") (pintype "input+no_connect"))
    )
    (net (code "63") (name "unconnected-(Slow1-Pad1)") (class "Default")
      (node (ref "Slow1") (pin "1") (pinfunction "1_1") (pintype "unspecified+no_connect"))
    )
    (net (code "64") (name "unconnected-(Step-Pad1)") (class "Default")
      (node (ref "Step") (pin "1") (pinfunction "1_1") (pintype "unspecified+no_connect"))
    )
    (net (code "65") (name "unconnected-(StepTrigger-Pad1)") (class "Default")
      (node (ref "StepTrigger") (pin "1") (pinfunction "1_1") (pintype "unspecified+no_connect"))
    )
    (net (code "66") (name "unconnected-(StepTrigger-Pad4)") (class "Default")
      (node (ref "StepTrigger") (pin "4") (pinfunction "4_4") (pintype "unspecified+no_connect"))
    )
    (net (code "67") (name "unconnected-(U2-RST-Pad4)") (class "Default")
      (node (ref "U2") (pin "4") (pinfunction "RST_4") (pintype "unspecified+no_connect"))
    )
    (net (code "68") (name "unconnected-(U3-3Y-Pad6)") (class "Default")
      (node (ref "U3") (pin "6") (pinfunction "3Y_6") (pintype "unspecified+no_connect"))
    )
    (net (code "69") (name "unconnected-(U3-4Y-Pad8)") (class "Default")
      (node (ref "U3") (pin "8") (pinfunction "4Y_8") (pintype "unspecified+no_connect"))
    )
    (net (code "70") (name "unconnected-(U5-3Y-Pad8)") (class "Default")
      (node (ref "U5") (pin "8") (pinfunction "3Y_8") (pintype "input+no_connect"))
    )
    (net (code "71") (name "unconnected-(U6-3Y-Pad8)") (class "Default")
      (node (ref "U6") (pin "8") (pinfunction "3Y_8") (pintype "input+no_connect"))
    )
    (net (code "72") (name "unconnected-(U6-4Y-Pad11)") (class "Default")
      (node (ref "U6") (pin "11") (pinfunction "4Y_11") (pintype "input+no_connect"))
    )
    (net (code "73") (name "unconnected-(U7-3Y-Pad8)") (class "Default")
      (node (ref "U7") (pin "8") (pinfunction "3Y_8") (pintype "input+no_connect"))
    )
    (net (code "74") (name "unconnected-(U8-3Y-Pad10)") (class "Default")
      (node (ref "U8") (pin "10") (pinfunction "3Y_10") (pintype "input+no_connect"))
    )
    (net (code "75") (name "unconnected-(U8-4Y-Pad13)") (class "Default")
      (node (ref "U8") (pin "13") (pinfunction "4Y_13") (pintype "input+no_connect"))
    )
    (net (code "76") (name "unconnected-(U10-1Q#-Pad6)") (class "Default")
      (node (ref "U10") (pin "6") (pinfunction "1Q#_6") (pintype "unspecified+no_connect"))
    )
    (net (code "77") (name "unconnected-(U10-2Q#-Pad8)") (class "Default")
      (node (ref "U10") (pin "8") (pinfunction "2Q#_8") (pintype "unspecified+no_connect"))
    )
    (net (code "78") (name "unconnected-(U10-2Q-Pad9)") (class "Default")
      (node (ref "U10") (pin "9") (pinfunction "2Q_9") (pintype "unspecified+no_connect"))
    )
    (net (code "79") (name "unconnected-(U11-3Y-Pad8)") (class "Default")
      (node (ref "U11") (pin "8") (pinfunction "3Y_8") (pintype "input+no_connect"))
    )
    (net (code "80") (name "unconnected-(U11-4Y-Pad11)") (class "Default")
      (node (ref "U11") (pin "11") (pinfunction "4Y_11") (pintype "input+no_connect"))
    )
  )
)
